# EPS_5V_EMI-Filter_Out.net
KiCad netlist of a schematic drawn in Altium Designer
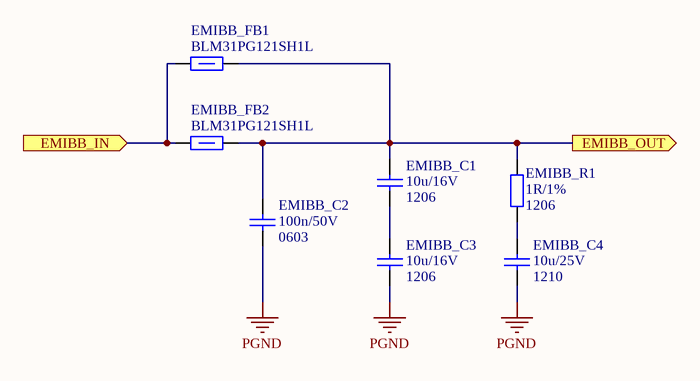
[diagram p0: EPS_5V_EMI-Filter_Out.SchDoc]

(export (version "E")
  (design (tool "Eeschema 10.0.6"))
  (components
    (comp (ref "EMIBB_C1")
      (value "10u/16V")
      (footprint "SMD_Capacitor_1206")
      (description "Ceramic Cap Kemet COTS 10u/16V X7R 1206")
      (fields
        (field (name "MANUFACTURERPARTNUMBER") "C1206T106K4RACTU")
        (field (name "MANUFACTURER") "Kemet")
        (field (name "PACKGE") "1206")
      )
      (libsource (lib "capacitors") (part "Cer_C1206T106K4RACTU"))
    )
    (comp (ref "EMIBB_C2")
      (value "100n/50V")
      (footprint "SMD_Capacitor_0603")
      (description "Ceramic Cap Kemet COTS 100n/50V X7R 0603")
      (fields
        (field (name "MANUFACTURER") "Kemet")
        (field (name "MANUFACTURERPARTNUMBER") "C0603T104K5RALTU")
        (field (name "PACKAGE") "0603")
      )
      (libsource (lib "capacitors") (part "Cer_C0603T104K5RALTU"))
    )
    (comp (ref "EMIBB_C3")
      (value "10u/16V")
      (footprint "SMD_Capacitor_1206")
      (description "Ceramic Cap Kemet COTS 10u/16V X7R 1206")
      (fields
        (field (name "MANUFACTURERPARTNUMBER") "C1206T106K4RACTU")
        (field (name "MANUFACTURER") "Kemet")
        (field (name "PACKGE") "1206")
      )
      (libsource (lib "capacitors") (part "Cer_C1206T106K4RACTU"))
    )
    (comp (ref "EMIBB_C4")
      (value "10u/25V")
      (footprint "SMD_Capacitor_1210")
      (description "Ceramic Cap Murata Automotive 10u/25V X7R 1210")
      (fields
        (field (name "MANUFACTURER") "Murata")
        (field (name "MANUFACTURERPARTNUMBER") "GCJ32ER71E106KA12L")
        (field (name "PACKAGE") "1210")
      )
      (libsource (lib "capacitors") (part "Cer_GCJ32ER71E106KA12L"))
    )
    (comp (ref "EMIBB_FB1")
      (value "120R/100MHz")
      (footprint "SMD_FerriteBead_1206")
      (description "Ferrite bead, 1206, 0.02HM, 3.5A.")
      (fields (field (name "MANUFACTURER") "Murata") (field (name "MANUFACTURERPARTNUMBER") "BLM31PG121SH1L"))
      (libsource (lib "inductors") (part "BLM31PG121SH1L"))
    )
    (comp (ref "EMIBB_FB2")
      (value "120R/100MHz")
      (footprint "SMD_FerriteBead_1206")
      (description "Ferrite bead, 1206, 0.02HM, 3.5A.")
      (fields (field (name "MANUFACTURER") "Murata") (field (name "MANUFACTURERPARTNUMBER") "BLM31PG121SH1L"))
      (libsource (lib "inductors") (part "BLM31PG121SH1L"))
    )
    (comp (ref "EMIBB_R1")
      (value "1R/1%")
      (footprint "SMD_Resistor_1206")
      (description "1R/1% Vishay CRCW 1206 Resistor. 250mW, 100ppm, 200V.")
      (fields
        (field (name "MANUFACTURERPARTNUMBER") "CRCW12061R00FKxxxx")
        (field (name "MANUFACTURER") "Vishay")
        (field (name "PACKAGE") "1206")
      )
      (libsource (lib "resistors") (part "CRCW12061R00FKxxxx"))
    )
  )
  (nets
    (net (code "1") (name "/EMIBB_IN") (class "Default")
      (node (ref "EMIBB_FB1") (pin "2") (pinfunction "2_2") (pintype "passive"))
      (node (ref "EMIBB_FB2") (pin "2") (pinfunction "2_2") (pintype "passive"))
    )
    (net (code "2") (name "/EMIBB_OUT") (class "Default")
      (node (ref "EMIBB_C1") (pin "1") (pinfunction "1_1") (pintype "passive"))
      (node (ref "EMIBB_C2") (pin "1") (pinfunction "1_1") (pintype "passive"))
      (node (ref "EMIBB_FB1") (pin "1") (pinfunction "1_1") (pintype "passive"))
      (node (ref "EMIBB_FB2") (pin "1") (pinfunction "1_1") (pintype "passive"))
      (node (ref "EMIBB_R1") (pin "1") (pinfunction "1_1") (pintype "passive"))
    )
    (net (code "3") (name "Net-(EMIBB_C1-Pad2)") (class "Default")
      (node (ref "EMIBB_C1") (pin "2") (pinfunction "2_2") (pintype "passive"))
      (node (ref "EMIBB_C3") (pin "1") (pinfunction "1_1") (pintype "passive"))
    )
    (net (code "4") (name "Net-(EMIBB_C4-Pad1)") (class "Default")
      (node (ref "EMIBB_C4") (pin "1") (pinfunction "1_1") (pintype "passive"))
      (node (ref "EMIBB_R1") (pin "2") (pinfunction "2_2") (pintype "passive"))
    )
    (net (code "5") (name "PGND") (class "Default")
      (node (ref "EMIBB_C2") (pin "2") (pinfunction "2_2") (pintype "passive"))
      (node (ref "EMIBB_C3") (pin "2") (pinfunction "2_2") (pintype "passive"))
      (node (ref "EMIBB_C4") (pin "2") (pinfunction "2_2") (pintype "passive"))
    )
  )
)
